# OR_Gate.net
KiCad netlist of a schematic drawn in EAGLE
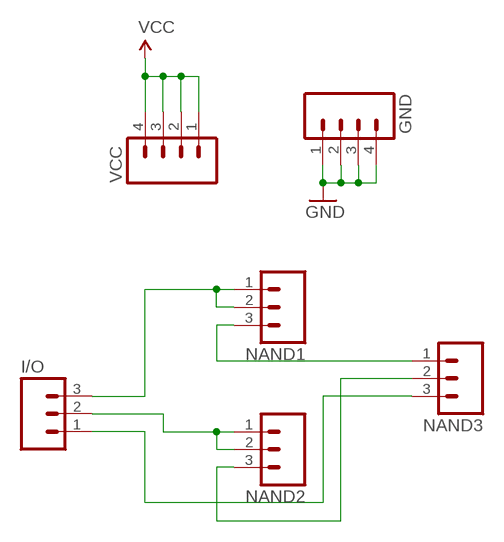
[diagram p0: schematic, sheet 1]

(export (version "E")
  (design (tool "Eeschema 10.0.6"))
  (components
    (comp (ref "GND")
      (value "M04LOCK")
      (footprint "eagle-import:1X04_LOCK")
      (libsource (lib "eagle-import") (part "M04LOCK"))
    )
    (comp (ref "I/O")
      (value "M03LOCK")
      (footprint "eagle-import:1X03_LOCK")
      (libsource (lib "eagle-import") (part "M03LOCK"))
    )
    (comp (ref "NAND1")
      (value "M03LOCK")
      (footprint "eagle-import:1X03_LOCK")
      (libsource (lib "eagle-import") (part "M03LOCK"))
    )
    (comp (ref "NAND2")
      (value "M03LOCK")
      (footprint "eagle-import:1X03_LOCK")
      (libsource (lib "eagle-import") (part "M03LOCK"))
    )
    (comp (ref "NAND3")
      (value "M03LOCK")
      (footprint "eagle-import:1X03_LOCK")
      (libsource (lib "eagle-import") (part "M03LOCK"))
    )
    (comp (ref "VCC")
      (value "M04LOCK")
      (footprint "eagle-import:1X04_LOCK")
      (libsource (lib "eagle-import") (part "M04LOCK"))
    )
  )
  (nets
    (net (code "1") (name "GND") (class "Default")
      (node (ref "GND") (pin "1") (pinfunction "1_1") (pintype "passive"))
      (node (ref "GND") (pin "2") (pinfunction "2_2") (pintype "passive"))
      (node (ref "GND") (pin "3") (pinfunction "3_3") (pintype "passive"))
      (node (ref "GND") (pin "4") (pinfunction "4_4") (pintype "passive"))
    )
    (net (code "2") (name "Net-(I/O-Pad1)") (class "Default")
      (node (ref "I/O") (pin "1") (pinfunction "1_1") (pintype "passive"))
      (node (ref "NAND3") (pin "3") (pinfunction "3_3") (pintype "passive"))
    )
    (net (code "3") (name "Net-(I/O-Pad2)") (class "Default")
      (node (ref "I/O") (pin "2") (pinfunction "2_2") (pintype "passive"))
      (node (ref "NAND2") (pin "1") (pinfunction "1_1") (pintype "passive"))
      (node (ref "NAND2") (pin "2") (pinfunction "2_2") (pintype "passive"))
    )
    (net (code "4") (name "Net-(I/O-Pad3)") (class "Default")
      (node (ref "I/O") (pin "3") (pinfunction "3_3") (pintype "passive"))
      (node (ref "NAND1") (pin "1") (pinfunction "1_1") (pintype "passive"))
      (node (ref "NAND1") (pin "2") (pinfunction "2_2") (pintype "passive"))
    )
    (net (code "5") (name "Net-(NAND1-Pad3)") (class "Default")
      (node (ref "NAND1") (pin "3") (pinfunction "3_3") (pintype "passive"))
      (node (ref "NAND3") (pin "1") (pinfunction "1_1") (pintype "passive"))
    )
    (net (code "6") (name "Net-(NAND2-Pad3)") (class "Default")
      (node (ref "NAND2") (pin "3") (pinfunction "3_3") (pintype "passive"))
      (node (ref "NAND3") (pin "2") (pinfunction "2_2") (pintype "passive"))
    )
    (net (code "7") (name "VCC") (class "Default")
      (node (ref "VCC") (pin "1") (pinfunction "1_1") (pintype "passive"))
      (node (ref "VCC") (pin "2") (pinfunction "2_2") (pintype "passive"))
      (node (ref "VCC") (pin "3") (pinfunction "3_3") (pintype "passive"))
      (node (ref "VCC") (pin "4") (pinfunction "4_4") (pintype "passive"))
    )
  )
)
